# 7-segment.net
KiCad netlist of a schematic drawn in EAGLE
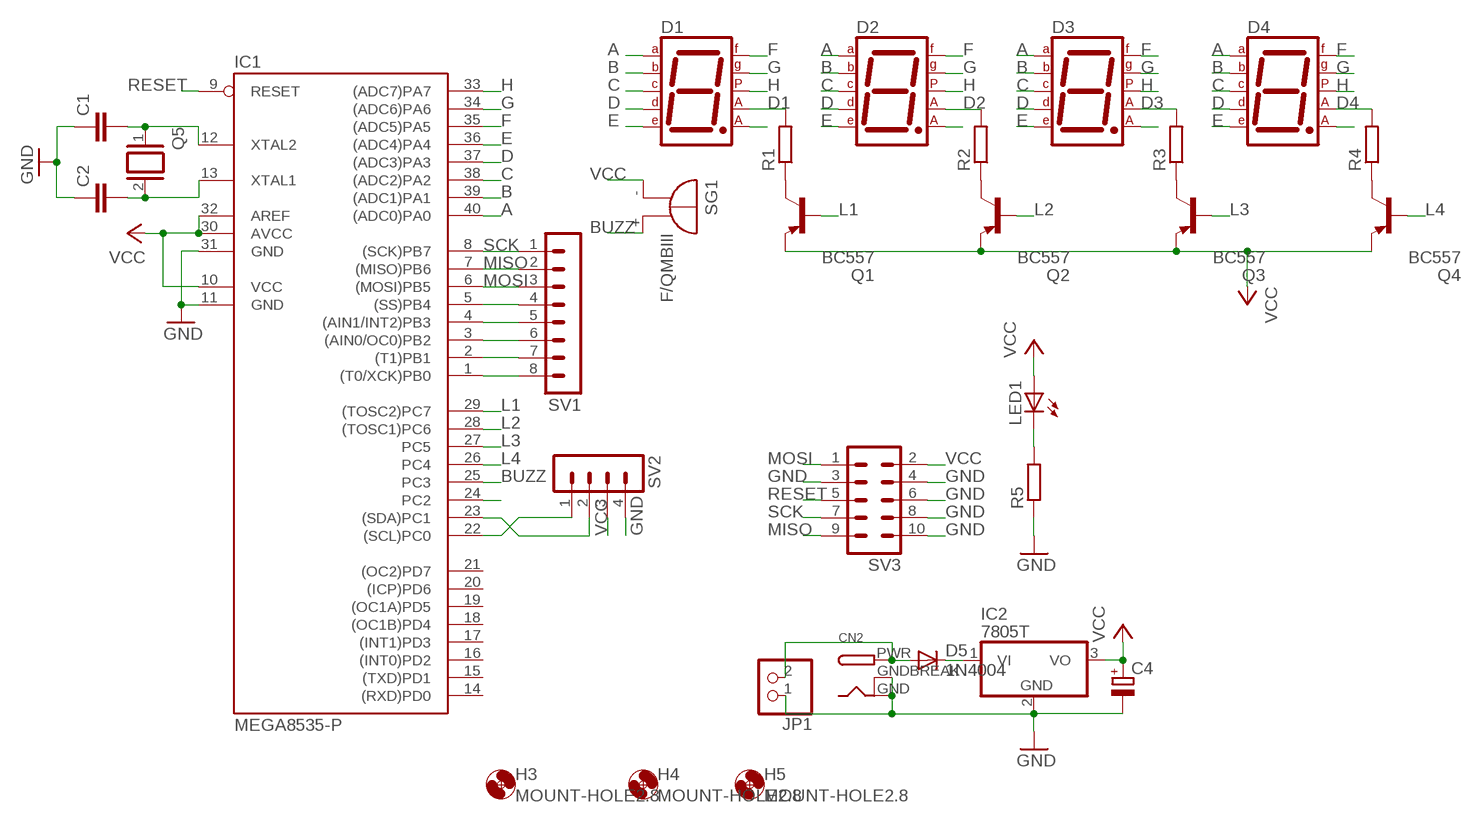
[diagram p0: schematic, sheet 1]

(export (version "E")
  (design (tool "Eeschema 10.0.6"))
  (components
    (comp (ref "C1")
      (value "C-EU025-024X044")
      (footprint "eagle-import:C025-024X044")
      (libsource (lib "eagle-import") (part "C-EU025-024X044"))
    )
    (comp (ref "C2")
      (value "C-EU025-024X044")
      (footprint "eagle-import:C025-024X044")
      (libsource (lib "eagle-import") (part "C-EU025-024X044"))
    )
    (comp (ref "C4")
      (value "CPOL-EUE2,5-6E")
      (footprint "eagle-import:E2,5-6E")
      (libsource (lib "eagle-import") (part "CPOL-EUE2,5-6E"))
    )
    (comp (ref "CN2")
      (value "DCBARRELPTH")
      (footprint "eagle-import:DCJACK_2MM_PTH")
      (libsource (lib "eagle-import") (part "DCBARRELPTH"))
    )
    (comp (ref "D1")
      (value "7SEG-CA0.8INCH")
      (footprint "eagle-import:7SEG-13")
      (libsource (lib "eagle-import") (part "7SEG-CA0.8INCH"))
    )
    (comp (ref "D2")
      (value "7SEG-CA0.8INCH")
      (footprint "eagle-import:7SEG-13")
      (libsource (lib "eagle-import") (part "7SEG-CA0.8INCH"))
    )
    (comp (ref "D3")
      (value "7SEG-CA0.8INCH")
      (footprint "eagle-import:7SEG-13")
      (libsource (lib "eagle-import") (part "7SEG-CA0.8INCH"))
    )
    (comp (ref "D4")
      (value "7SEG-CA0.8INCH")
      (footprint "eagle-import:7SEG-13")
      (libsource (lib "eagle-import") (part "7SEG-CA0.8INCH"))
    )
    (comp (ref "D5")
      (value "1N4004")
      (footprint "eagle-import:DO41-10")
      (libsource (lib "eagle-import") (part "1N4004"))
    )
    (comp (ref "H3")
      (value "MOUNT-HOLE2.8")
      (footprint "eagle-import:2,8")
      (libsource (lib "eagle-import") (part "MOUNT-HOLE2.8"))
    )
    (comp (ref "H4")
      (value "MOUNT-HOLE2.8")
      (footprint "eagle-import:2,8")
      (libsource (lib "eagle-import") (part "MOUNT-HOLE2.8"))
    )
    (comp (ref "H5")
      (value "MOUNT-HOLE2.8")
      (footprint "eagle-import:2,8")
      (libsource (lib "eagle-import") (part "MOUNT-HOLE2.8"))
    )
    (comp (ref "IC1")
      (value "MEGA8535-P")
      (footprint "eagle-import:DIL40")
      (fields (field (name "MPN") "ATMEGA8535-16PU"))
      (libsource (lib "eagle-import") (part "MEGA8535-P"))
    )
    (comp (ref "IC2")
      (value "7805T")
      (footprint "eagle-import:TO220H")
      (libsource (lib "eagle-import") (part "78T05"))
    )
    (comp (ref "JP1")
      (value "PINHD-1X2")
      (footprint "eagle-import:1X02")
      (libsource (lib "eagle-import") (part "PINHD-1X2"))
    )
    (comp (ref "LED1")
      (value "LED3MM")
      (footprint "eagle-import:LED3MM")
      (libsource (lib "eagle-import") (part "LED3MM"))
    )
    (comp (ref "Q1")
      (value "BC557")
      (footprint "eagle-import:TO92-EBC")
      (libsource (lib "eagle-import") (part "BC557"))
    )
    (comp (ref "Q2")
      (value "BC557")
      (footprint "eagle-import:TO92-EBC")
      (libsource (lib "eagle-import") (part "BC557"))
    )
    (comp (ref "Q3")
      (value "BC557")
      (footprint "eagle-import:TO92-EBC")
      (libsource (lib "eagle-import") (part "BC557"))
    )
    (comp (ref "Q4")
      (value "BC557")
      (footprint "eagle-import:TO92-EBC")
      (libsource (lib "eagle-import") (part "BC557"))
    )
    (comp (ref "Q5")
      (value "XTAL/S")
      (footprint "eagle-import:QS")
      (libsource (lib "eagle-import") (part "XTAL/S"))
    )
    (comp (ref "R1")
      (value "R-EU_0207/7")
      (footprint "eagle-import:0207_7")
      (libsource (lib "eagle-import") (part "R-EU_0207/7"))
    )
    (comp (ref "R2")
      (value "R-EU_0207/7")
      (footprint "eagle-import:0207_7")
      (libsource (lib "eagle-import") (part "R-EU_0207/7"))
    )
    (comp (ref "R3")
      (value "R-EU_0207/7")
      (footprint "eagle-import:0207_7")
      (libsource (lib "eagle-import") (part "R-EU_0207/7"))
    )
    (comp (ref "R4")
      (value "R-EU_0207/7")
      (footprint "eagle-import:0207_7")
      (libsource (lib "eagle-import") (part "R-EU_0207/7"))
    )
    (comp (ref "R5")
      (value "R-EU_0207/7")
      (footprint "eagle-import:0207_7")
      (libsource (lib "eagle-import") (part "rcl_footprint_R-EU_0207/7"))
    )
    (comp (ref "SG1")
      (value "F/QMBIII")
      (footprint "eagle-import:F_QMBIII")
      (libsource (lib "eagle-import") (part "F/QMBIII"))
    )
    (comp (ref "SV1")
      (value "MA08-1")
      (footprint "eagle-import:MA08-1")
      (libsource (lib "eagle-import") (part "MA08-1"))
    )
    (comp (ref "SV2")
      (value "MA04-1")
      (footprint "eagle-import:MA04-1")
      (libsource (lib "eagle-import") (part "MA04-1"))
    )
    (comp (ref "SV3")
      (value "MA05-2")
      (footprint "eagle-import:MA05-2")
      (libsource (lib "eagle-import") (part "MA05-2"))
    )
  )
  (nets
    (net (code "1") (name "/A") (class "Default")
      (node (ref "D1") (pin "7") (pinfunction "A_7") (pintype "passive"))
      (node (ref "D2") (pin "7") (pinfunction "A_7") (pintype "passive"))
      (node (ref "D3") (pin "7") (pinfunction "A_7") (pintype "passive"))
      (node (ref "D4") (pin "7") (pinfunction "A_7") (pintype "passive"))
      (node (ref "IC1") (pin "40") (pinfunction "(ADC0)PA0_40") (pintype "bidirectional"))
    )
    (net (code "2") (name "/B") (class "Default")
      (node (ref "D1") (pin "6") (pinfunction "B_6") (pintype "passive"))
      (node (ref "D2") (pin "6") (pinfunction "B_6") (pintype "passive"))
      (node (ref "D3") (pin "6") (pinfunction "B_6") (pintype "passive"))
      (node (ref "D4") (pin "6") (pinfunction "B_6") (pintype "passive"))
      (node (ref "IC1") (pin "39") (pinfunction "(ADC1)PA1_39") (pintype "bidirectional"))
    )
    (net (code "3") (name "/BUZZ") (class "Default")
      (node (ref "IC1") (pin "25") (pinfunction "PC3_25") (pintype "bidirectional"))
      (node (ref "SG1") (pin "+") (pinfunction "-_+") (pintype "passive"))
    )
    (net (code "4") (name "/C") (class "Default")
      (node (ref "D1") (pin "4") (pinfunction "C_4") (pintype "passive"))
      (node (ref "D2") (pin "4") (pinfunction "C_4") (pintype "passive"))
      (node (ref "D3") (pin "4") (pinfunction "C_4") (pintype "passive"))
      (node (ref "D4") (pin "4") (pinfunction "C_4") (pintype "passive"))
      (node (ref "IC1") (pin "38") (pinfunction "(ADC2)PA2_38") (pintype "bidirectional"))
    )
    (net (code "5") (name "/D") (class "Default")
      (node (ref "D1") (pin "2") (pinfunction "D_2") (pintype "passive"))
      (node (ref "D2") (pin "2") (pinfunction "D_2") (pintype "passive"))
      (node (ref "D3") (pin "2") (pinfunction "D_2") (pintype "passive"))
      (node (ref "D4") (pin "2") (pinfunction "D_2") (pintype "passive"))
      (node (ref "IC1") (pin "37") (pinfunction "(ADC3)PA3_37") (pintype "bidirectional"))
    )
    (net (code "6") (name "/D1") (class "Default")
      (node (ref "D1") (pin "3") (pinfunction "CA1_3") (pintype "passive"))
      (node (ref "R1") (pin "2") (pinfunction "2_2") (pintype "passive"))
    )
    (net (code "7") (name "/D2") (class "Default")
      (node (ref "D2") (pin "3") (pinfunction "CA1_3") (pintype "passive"))
      (node (ref "R2") (pin "2") (pinfunction "2_2") (pintype "passive"))
    )
    (net (code "8") (name "/D3") (class "Default")
      (node (ref "D3") (pin "3") (pinfunction "CA1_3") (pintype "passive"))
      (node (ref "R3") (pin "2") (pinfunction "2_2") (pintype "passive"))
    )
    (net (code "9") (name "/D4") (class "Default")
      (node (ref "D4") (pin "3") (pinfunction "CA1_3") (pintype "passive"))
      (node (ref "R4") (pin "2") (pinfunction "2_2") (pintype "passive"))
    )
    (net (code "10") (name "/E") (class "Default")
      (node (ref "D1") (pin "1") (pinfunction "E_1") (pintype "passive"))
      (node (ref "D2") (pin "1") (pinfunction "E_1") (pintype "passive"))
      (node (ref "D3") (pin "1") (pinfunction "E_1") (pintype "passive"))
      (node (ref "D4") (pin "1") (pinfunction "E_1") (pintype "passive"))
      (node (ref "IC1") (pin "36") (pinfunction "(ADC4)PA4_36") (pintype "bidirectional"))
    )
    (net (code "11") (name "/F") (class "Default")
      (node (ref "D1") (pin "9") (pinfunction "F_9") (pintype "passive"))
      (node (ref "D2") (pin "9") (pinfunction "F_9") (pintype "passive"))
      (node (ref "D3") (pin "9") (pinfunction "F_9") (pintype "passive"))
      (node (ref "D4") (pin "9") (pinfunction "F_9") (pintype "passive"))
      (node (ref "IC1") (pin "35") (pinfunction "(ADC5)PA5_35") (pintype "bidirectional"))
    )
    (net (code "12") (name "/G") (class "Default")
      (node (ref "D1") (pin "10") (pinfunction "G_10") (pintype "passive"))
      (node (ref "D2") (pin "10") (pinfunction "G_10") (pintype "passive"))
      (node (ref "D3") (pin "10") (pinfunction "G_10") (pintype "passive"))
      (node (ref "D4") (pin "10") (pinfunction "G_10") (pintype "passive"))
      (node (ref "IC1") (pin "34") (pinfunction "(ADC6)PA6_34") (pintype "bidirectional"))
    )
    (net (code "13") (name "/H") (class "Default")
      (node (ref "D1") (pin "5") (pinfunction "DP_5") (pintype "passive"))
      (node (ref "D2") (pin "5") (pinfunction "DP_5") (pintype "passive"))
      (node (ref "D3") (pin "5") (pinfunction "DP_5") (pintype "passive"))
      (node (ref "D4") (pin "5") (pinfunction "DP_5") (pintype "passive"))
      (node (ref "IC1") (pin "33") (pinfunction "(ADC7)PA7_33") (pintype "bidirectional"))
    )
    (net (code "14") (name "/L1") (class "Default")
      (node (ref "IC1") (pin "29") (pinfunction "(TOSC2)PC7_29") (pintype "bidirectional"))
      (node (ref "Q1") (pin "B") (pinfunction "B_B") (pintype "passive"))
    )
    (net (code "15") (name "/L2") (class "Default")
      (node (ref "IC1") (pin "28") (pinfunction "(TOSC1)PC6_28") (pintype "bidirectional"))
      (node (ref "Q2") (pin "B") (pinfunction "B_B") (pintype "passive"))
    )
    (net (code "16") (name "/L3") (class "Default")
      (node (ref "IC1") (pin "27") (pinfunction "PC5_27") (pintype "bidirectional"))
      (node (ref "Q3") (pin "B") (pinfunction "B_B") (pintype "passive"))
    )
    (net (code "17") (name "/L4") (class "Default")
      (node (ref "IC1") (pin "26") (pinfunction "PC4_26") (pintype "bidirectional"))
      (node (ref "Q4") (pin "B") (pinfunction "B_B") (pintype "passive"))
    )
    (net (code "18") (name "/MISO") (class "Default")
      (node (ref "IC1") (pin "7") (pinfunction "(MISO)PB6_7") (pintype "bidirectional"))
      (node (ref "SV1") (pin "2") (pinfunction "2_2") (pintype "passive"))
      (node (ref "SV3") (pin "9") (pinfunction "9_9") (pintype "passive"))
    )
    (net (code "19") (name "/MOSI") (class "Default")
      (node (ref "IC1") (pin "6") (pinfunction "(MOSI)PB5_6") (pintype "bidirectional"))
      (node (ref "SV1") (pin "3") (pinfunction "3_3") (pintype "passive"))
      (node (ref "SV3") (pin "1") (pinfunction "1_1") (pintype "passive"))
    )
    (net (code "20") (name "/RESET") (class "Default")
      (node (ref "IC1") (pin "9") (pinfunction "RESET_9") (pintype "input"))
      (node (ref "SV3") (pin "5") (pinfunction "5_5") (pintype "passive"))
    )
    (net (code "21") (name "/SCK") (class "Default")
      (node (ref "IC1") (pin "8") (pinfunction "(SCK)PB7_8") (pintype "bidirectional"))
      (node (ref "SV1") (pin "1") (pinfunction "1_1") (pintype "passive"))
      (node (ref "SV3") (pin "7") (pinfunction "7_7") (pintype "passive"))
    )
    (net (code "22") (name "GND") (class "Default")
      (node (ref "C1") (pin "1") (pinfunction "1_1") (pintype "passive"))
      (node (ref "C2") (pin "1") (pinfunction "1_1") (pintype "passive"))
      (node (ref "C4") (pin "-") (pinfunction "-_-") (pintype "passive"))
      (node (ref "CN2") (pin "GND") (pinfunction "GND_GND") (pintype "power_in"))
      (node (ref "CN2") (pin "GNDBREAK") (pinfunction "GNDBREAK_GNDBREAK") (pintype "power_in"))
      (node (ref "IC1") (pin "11") (pinfunction "GND_11") (pintype "power_in"))
      (node (ref "IC1") (pin "31") (pinfunction "GND_31") (pintype "power_in"))
      (node (ref "IC2") (pin "2") (pinfunction "GND_2") (pintype "passive"))
      (node (ref "JP1") (pin "1") (pinfunction "1_1") (pintype "passive"))
      (node (ref "R5") (pin "1") (pinfunction "1_1") (pintype "passive"))
      (node (ref "SV2") (pin "4") (pinfunction "4_4") (pintype "passive"))
      (node (ref "SV3") (pin "10") (pinfunction "10_10") (pintype "passive"))
      (node (ref "SV3") (pin "3") (pinfunction "3_3") (pintype "passive"))
      (node (ref "SV3") (pin "4") (pinfunction "4_4") (pintype "passive"))
      (node (ref "SV3") (pin "6") (pinfunction "6_6") (pintype "passive"))
      (node (ref "SV3") (pin "8") (pinfunction "8_8") (pintype "passive"))
    )
    (net (code "23") (name "Net-(CN2-PadPWR)") (class "Default")
      (node (ref "CN2") (pin "PWR") (pinfunction "PWR_PWR") (pintype "power_in"))
      (node (ref "D5") (pin "A") (pinfunction "A_A") (pintype "passive"))
      (node (ref "JP1") (pin "2") (pinfunction "2_2") (pintype "passive"))
    )
    (net (code "24") (name "Net-(IC1-(AIN0{slash}OC0)PB2)") (class "Default")
      (node (ref "IC1") (pin "3") (pinfunction "(AIN0/OC0)PB2_3") (pintype "bidirectional"))
      (node (ref "SV1") (pin "6") (pinfunction "6_6") (pintype "passive"))
    )
    (net (code "25") (name "Net-(IC1-(AIN1{slash}INT2)PB3)") (class "Default")
      (node (ref "IC1") (pin "4") (pinfunction "(AIN1/INT2)PB3_4") (pintype "bidirectional"))
      (node (ref "SV1") (pin "5") (pinfunction "5_5") (pintype "passive"))
    )
    (net (code "26") (name "Net-(IC1-(SCL)PC0)") (class "Default")
      (node (ref "IC1") (pin "22") (pinfunction "(SCL)PC0_22") (pintype "bidirectional"))
      (node (ref "SV2") (pin "1") (pinfunction "1_1") (pintype "passive"))
    )
    (net (code "27") (name "Net-(IC1-(SDA)PC1)") (class "Default")
      (node (ref "IC1") (pin "23") (pinfunction "(SDA)PC1_23") (pintype "bidirectional"))
      (node (ref "SV2") (pin "2") (pinfunction "2_2") (pintype "passive"))
    )
    (net (code "28") (name "Net-(IC1-(SS)PB4)") (class "Default")
      (node (ref "IC1") (pin "5") (pinfunction "(SS)PB4_5") (pintype "bidirectional"))
      (node (ref "SV1") (pin "4") (pinfunction "4_4") (pintype "passive"))
    )
    (net (code "29") (name "Net-(IC1-(T0{slash}XCK)PB0)") (class "Default")
      (node (ref "IC1") (pin "1") (pinfunction "(T0/XCK)PB0_1") (pintype "bidirectional"))
      (node (ref "SV1") (pin "8") (pinfunction "8_8") (pintype "passive"))
    )
    (net (code "30") (name "Net-(IC1-(T1)PB1)") (class "Default")
      (node (ref "IC1") (pin "2") (pinfunction "(T1)PB1_2") (pintype "bidirectional"))
      (node (ref "SV1") (pin "7") (pinfunction "7_7") (pintype "passive"))
    )
    (net (code "31") (name "Net-(IC1-XTAL1)") (class "Default")
      (node (ref "C2") (pin "2") (pinfunction "2_2") (pintype "passive"))
      (node (ref "IC1") (pin "13") (pinfunction "XTAL1_13") (pintype "bidirectional"))
      (node (ref "Q5") (pin "2") (pinfunction "2_2") (pintype "passive"))
    )
    (net (code "32") (name "Net-(IC1-XTAL2)") (class "Default")
      (node (ref "C1") (pin "2") (pinfunction "2_2") (pintype "passive"))
      (node (ref "IC1") (pin "12") (pinfunction "XTAL2_12") (pintype "bidirectional"))
      (node (ref "Q5") (pin "1") (pinfunction "1_1") (pintype "passive"))
    )
    (net (code "33") (name "Net-(IC2-VI)") (class "Default")
      (node (ref "D5") (pin "C") (pinfunction "C_C") (pintype "passive"))
      (node (ref "IC2") (pin "1") (pinfunction "VI_1") (pintype "input"))
    )
    (net (code "34") (name "Net-(LED1-C)") (class "Default")
      (node (ref "LED1") (pin "K") (pinfunction "C_K") (pintype "passive"))
      (node (ref "R5") (pin "2") (pinfunction "2_2") (pintype "passive"))
    )
    (net (code "35") (name "Net-(Q1-PadC)") (class "Default")
      (node (ref "Q1") (pin "C") (pinfunction "C_C") (pintype "passive"))
      (node (ref "R1") (pin "1") (pinfunction "1_1") (pintype "passive"))
    )
    (net (code "36") (name "Net-(Q2-PadC)") (class "Default")
      (node (ref "Q2") (pin "C") (pinfunction "C_C") (pintype "passive"))
      (node (ref "R2") (pin "1") (pinfunction "1_1") (pintype "passive"))
    )
    (net (code "37") (name "Net-(Q3-PadC)") (class "Default")
      (node (ref "Q3") (pin "C") (pinfunction "C_C") (pintype "passive"))
      (node (ref "R3") (pin "1") (pinfunction "1_1") (pintype "passive"))
    )
    (net (code "38") (name "Net-(Q4-PadC)") (class "Default")
      (node (ref "Q4") (pin "C") (pinfunction "C_C") (pintype "passive"))
      (node (ref "R4") (pin "1") (pinfunction "1_1") (pintype "passive"))
    )
    (net (code "39") (name "VCC") (class "Default")
      (node (ref "C4") (pin "+") (pinfunction "+_+") (pintype "passive"))
      (node (ref "IC1") (pin "10") (pinfunction "VCC_10") (pintype "power_in"))
      (node (ref "IC1") (pin "30") (pinfunction "AVCC_30") (pintype "power_in"))
      (node (ref "IC1") (pin "32") (pinfunction "AREF_32") (pintype "passive"))
      (node (ref "IC2") (pin "3") (pinfunction "VO_3") (pintype "passive"))
      (node (ref "LED1") (pin "A") (pinfunction "A_A") (pintype "passive"))
      (node (ref "Q1") (pin "E") (pinfunction "E_E") (pintype "passive"))
      (node (ref "Q2") (pin "E") (pinfunction "E_E") (pintype "passive"))
      (node (ref "Q3") (pin "E") (pinfunction "E_E") (pintype "passive"))
      (node (ref "Q4") (pin "E") (pinfunction "E_E") (pintype "passive"))
      (node (ref "SG1") (pin "-") (pinfunction "+_-") (pintype "passive"))
      (node (ref "SV2") (pin "3") (pinfunction "3_3") (pintype "passive"))
      (node (ref "SV3") (pin "2") (pinfunction "2_2") (pintype "passive"))
    )
    (net (code "40") (name "unconnected-(D1-CA2-Pad8)") (class "Default")
      (node (ref "D1") (pin "8") (pinfunction "CA2_8") (pintype "passive"))
    )
    (net (code "41") (name "unconnected-(D2-CA2-Pad8)") (class "Default")
      (node (ref "D2") (pin "8") (pinfunction "CA2_8") (pintype "passive"))
    )
    (net (code "42") (name "unconnected-(D3-CA2-Pad8)") (class "Default")
      (node (ref "D3") (pin "8") (pinfunction "CA2_8") (pintype "passive"))
    )
    (net (code "43") (name "unconnected-(D4-CA2-Pad8)") (class "Default")
      (node (ref "D4") (pin "8") (pinfunction "CA2_8") (pintype "passive"))
    )
    (net (code "44") (name "unconnected-(IC1-(ICP)PD6-Pad20)") (class "Default")
      (node (ref "IC1") (pin "20") (pinfunction "(ICP)PD6_20") (pintype "bidirectional"))
    )
    (net (code "45") (name "unconnected-(IC1-(INT0)PD2-Pad16)") (class "Default")
      (node (ref "IC1") (pin "16") (pinfunction "(INT0)PD2_16") (pintype "bidirectional"))
    )
    (net (code "46") (name "unconnected-(IC1-(INT1)PD3-Pad17)") (class "Default")
      (node (ref "IC1") (pin "17") (pinfunction "(INT1)PD3_17") (pintype "bidirectional"))
    )
    (net (code "47") (name "unconnected-(IC1-(OC1A)PD5-Pad19)") (class "Default")
      (node (ref "IC1") (pin "19") (pinfunction "(OC1A)PD5_19") (pintype "bidirectional"))
    )
    (net (code "48") (name "unconnected-(IC1-(OC1B)PD4-Pad18)") (class "Default")
      (node (ref "IC1") (pin "18") (pinfunction "(OC1B)PD4_18") (pintype "bidirectional"))
    )
    (net (code "49") (name "unconnected-(IC1-(OC2)PD7-Pad21)") (class "Default")
      (node (ref "IC1") (pin "21") (pinfunction "(OC2)PD7_21") (pintype "bidirectional"))
    )
    (net (code "50") (name "unconnected-(IC1-(RXD)PD0-Pad14)") (class "Default")
      (node (ref "IC1") (pin "14") (pinfunction "(RXD)PD0_14") (pintype "bidirectional"))
    )
    (net (code "51") (name "unconnected-(IC1-(TXD)PD1-Pad15)") (class "Default")
      (node (ref "IC1") (pin "15") (pinfunction "(TXD)PD1_15") (pintype "bidirectional"))
    )
    (net (code "52") (name "unconnected-(IC1-PC2-Pad24)") (class "Default")
      (node (ref "IC1") (pin "24") (pinfunction "PC2_24") (pintype "bidirectional"))
    )
  )
)
